# sata-hub3.net
KiCad netlist of a schematic drawn in EAGLE
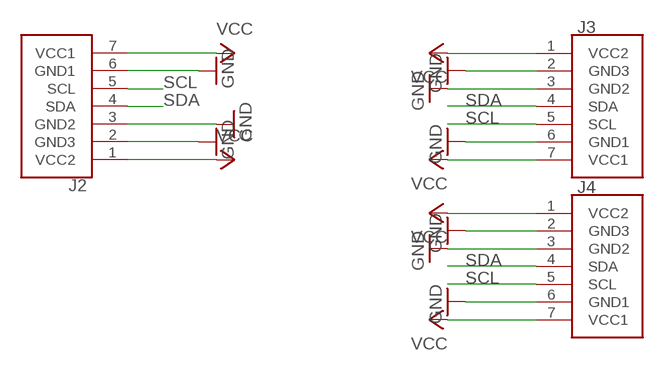
[diagram p0: schematic, sheet 1]

(export (version "E")
  (design (tool "Eeschema 10.0.6"))
  (components
    (comp (ref "J2")
      (value "SATA7-RA")
      (footprint "eagle-import:SATA7-RA")
      (libsource (lib "eagle-import") (part "SATA7-RA"))
    )
    (comp (ref "J3")
      (value "SATA7-RA")
      (footprint "eagle-import:SATA7-RA")
      (libsource (lib "eagle-import") (part "SATA7-RA"))
    )
    (comp (ref "J4")
      (value "SATA7-RA")
      (footprint "eagle-import:SATA7-RA")
      (libsource (lib "eagle-import") (part "SATA7-RA"))
    )
  )
  (nets
    (net (code "1") (name "/SCL") (class "Default")
      (node (ref "J2") (pin "5") (pinfunction "SCL_5") (pintype "bidirectional"))
      (node (ref "J3") (pin "5") (pinfunction "SCL_5") (pintype "bidirectional"))
      (node (ref "J4") (pin "5") (pinfunction "SCL_5") (pintype "bidirectional"))
    )
    (net (code "2") (name "/SDA") (class "Default")
      (node (ref "J2") (pin "4") (pinfunction "SDA_4") (pintype "bidirectional"))
      (node (ref "J3") (pin "4") (pinfunction "SDA_4") (pintype "bidirectional"))
      (node (ref "J4") (pin "4") (pinfunction "SDA_4") (pintype "bidirectional"))
    )
    (net (code "3") (name "GND") (class "Default")
      (node (ref "J2") (pin "2") (pinfunction "GND3_2") (pintype "power_in"))
      (node (ref "J2") (pin "3") (pinfunction "GND2_3") (pintype "power_in"))
      (node (ref "J2") (pin "6") (pinfunction "GND1_6") (pintype "power_in"))
      (node (ref "J3") (pin "2") (pinfunction "GND3_2") (pintype "power_in"))
      (node (ref "J3") (pin "3") (pinfunction "GND2_3") (pintype "power_in"))
      (node (ref "J3") (pin "6") (pinfunction "GND1_6") (pintype "power_in"))
      (node (ref "J4") (pin "2") (pinfunction "GND3_2") (pintype "power_in"))
      (node (ref "J4") (pin "3") (pinfunction "GND2_3") (pintype "power_in"))
      (node (ref "J4") (pin "6") (pinfunction "GND1_6") (pintype "power_in"))
    )
    (net (code "4") (name "VCC") (class "Default")
      (node (ref "J2") (pin "1") (pinfunction "VCC2_1") (pintype "power_in"))
      (node (ref "J2") (pin "7") (pinfunction "VCC1_7") (pintype "power_in"))
      (node (ref "J3") (pin "1") (pinfunction "VCC2_1") (pintype "power_in"))
      (node (ref "J3") (pin "7") (pinfunction "VCC1_7") (pintype "power_in"))
      (node (ref "J4") (pin "1") (pinfunction "VCC2_1") (pintype "power_in"))
      (node (ref "J4") (pin "7") (pinfunction "VCC1_7") (pintype "power_in"))
    )
  )
)
